# PCBPhase.net
KiCad netlist of a schematic drawn in EasyEDA Pro
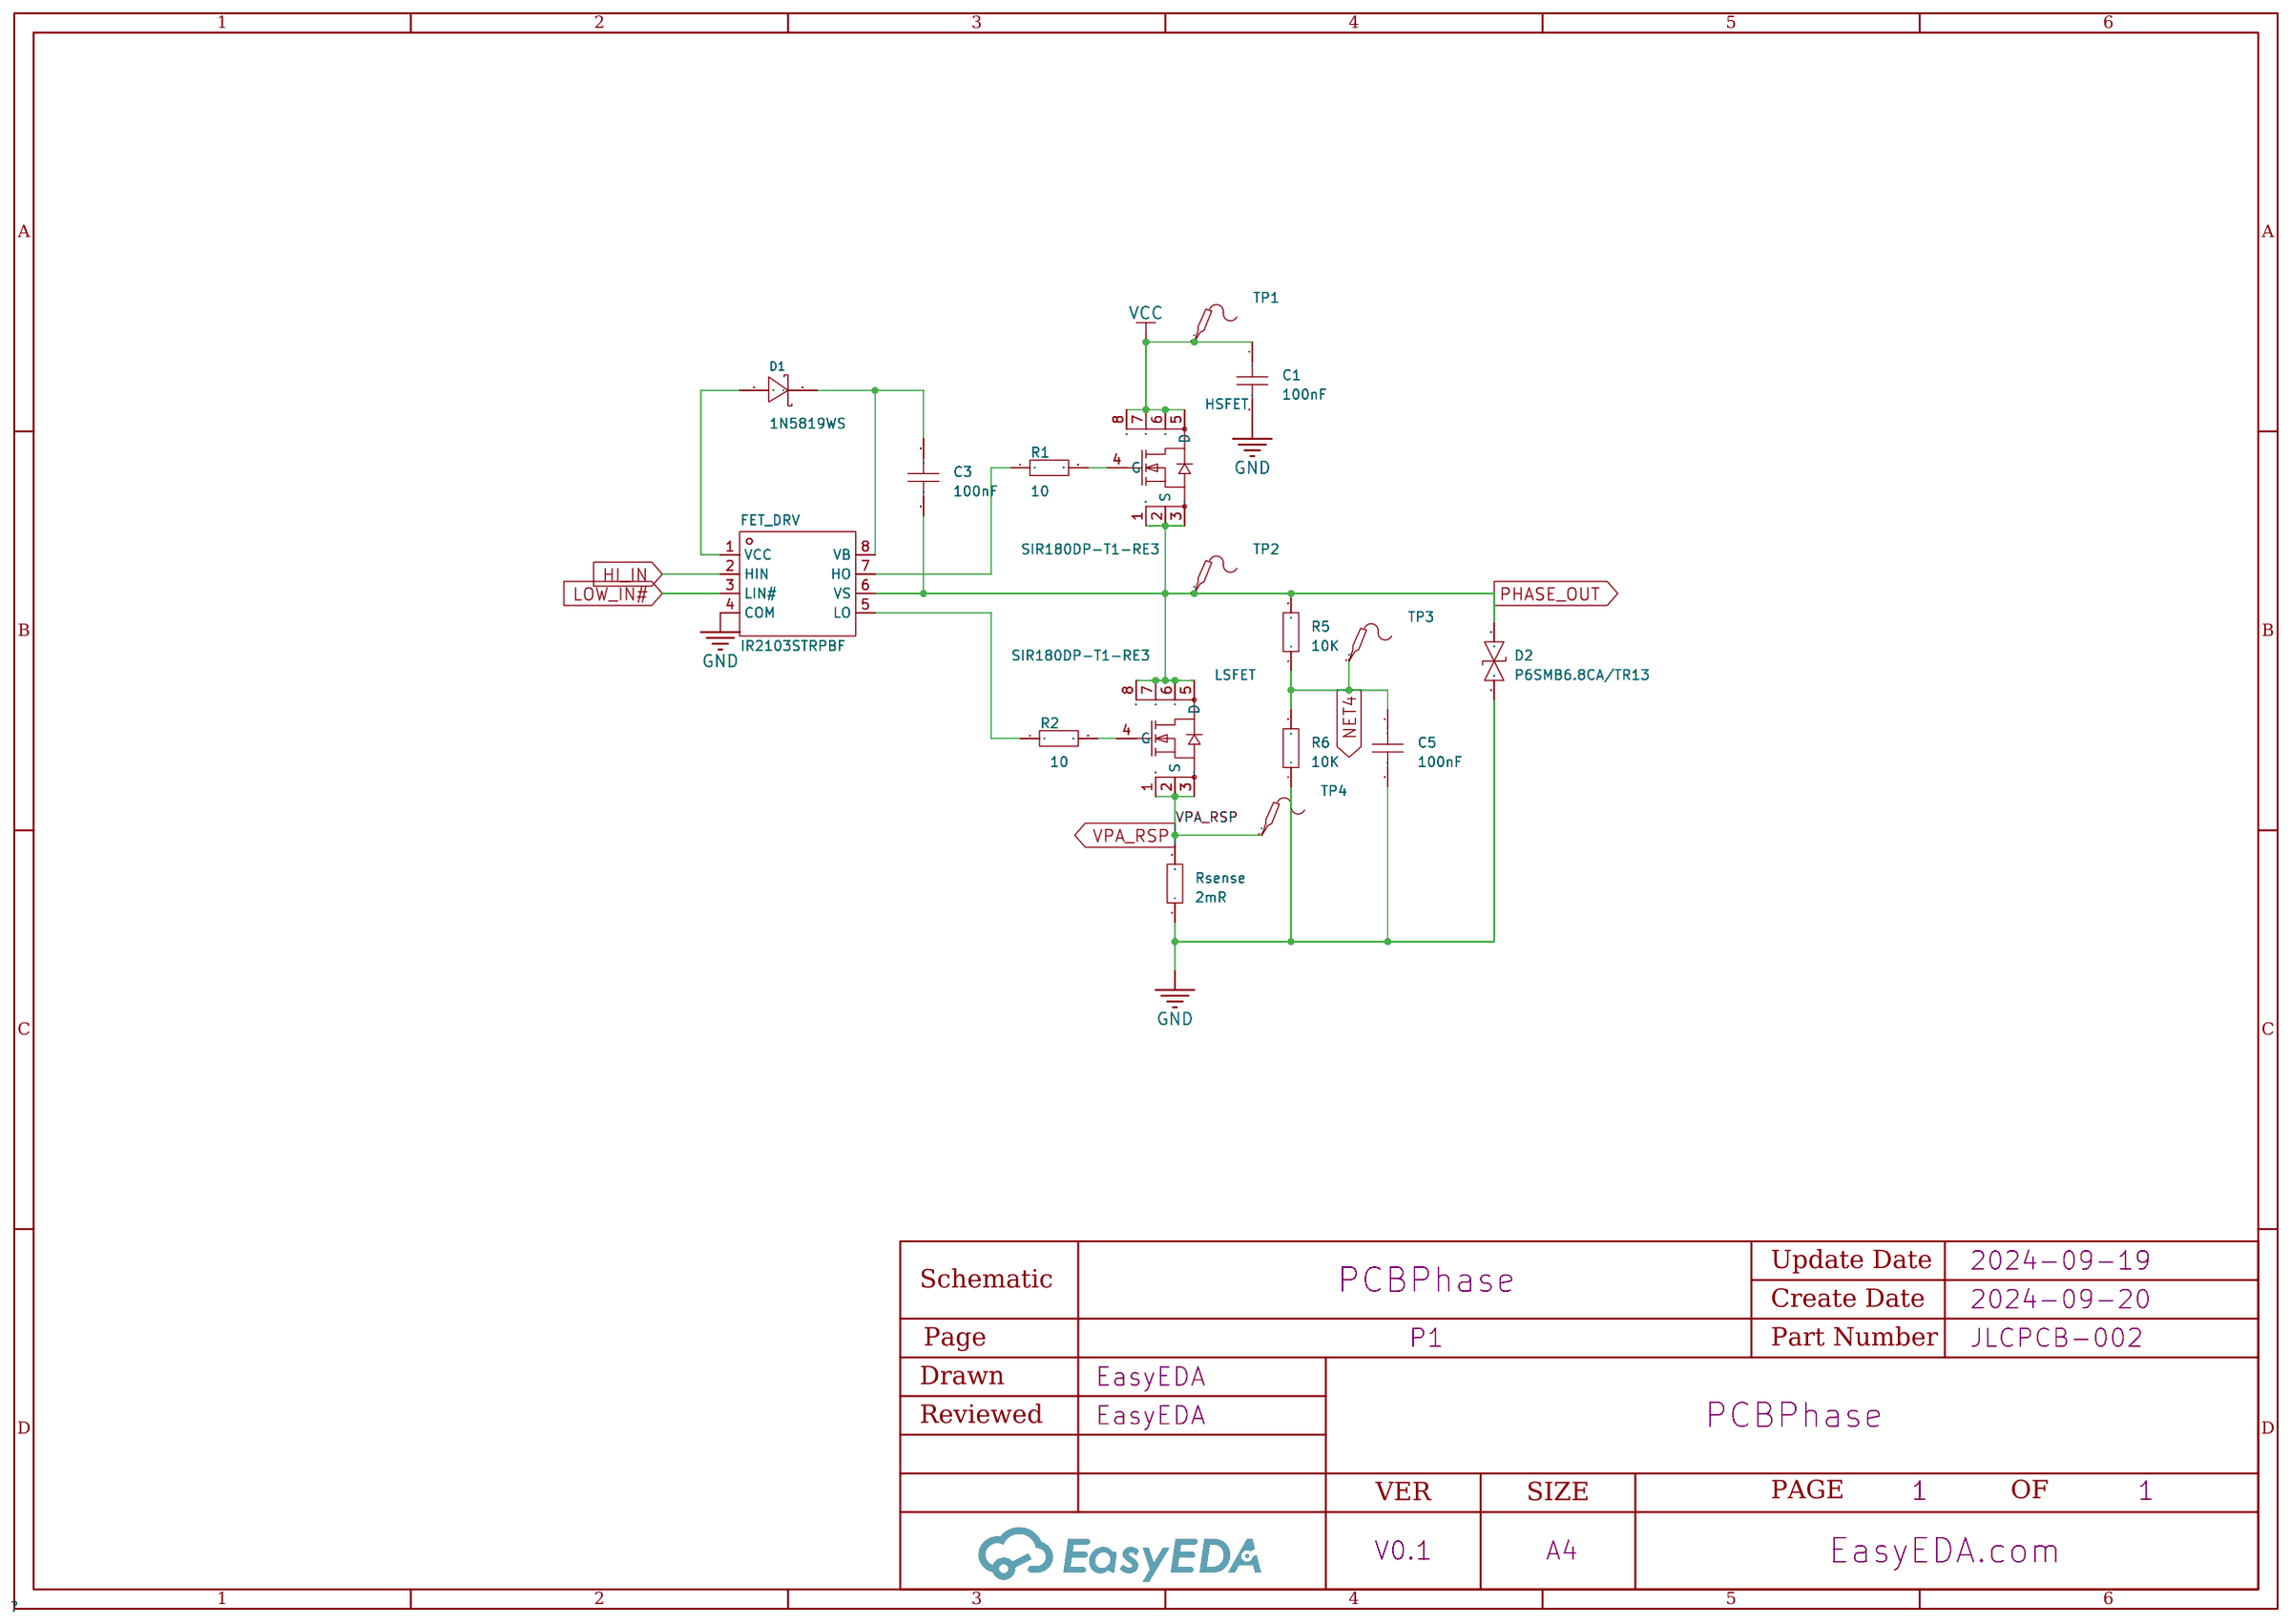
[diagram p0: schematic sheet]

(export (version "E")
  (design (tool "Eeschema 10.0.6"))
  (components
    (comp (ref "C1")
      (value "100nF")
      (footprint "easyedapro:C0603")
      (libsource (lib "easyedapro") (part "CAP"))
    )
    (comp (ref "C3")
      (value "100nF")
      (footprint "easyedapro:C0603")
      (libsource (lib "easyedapro") (part "CAP"))
    )
    (comp (ref "C5")
      (value "100nF")
      (footprint "easyedapro:C0603")
      (libsource (lib "easyedapro") (part "CAP"))
    )
    (comp (ref "D1")
      (value "1N5819WS")
      (footprint "easyedapro:SOD-323_L1.8-W1.3-LS2.5-RD")
      (description "Forward Voltage (Vf@If):600mV@1A Reverse Voltage (Vr):40V Average Rectified Current (Io):1A")
      (fields (field (name "Manufacturer") "Hottech(合科泰)"))
      (libsource (lib "easyedapro") (part "1N5819WS"))
    )
    (comp (ref "D2")
      (value "P6SMB6.8CA/TR13")
      (footprint "easyedapro:SMB_L4.6-W3.6-LS5.3-BI")
      (fields (field (name "Manufacturer") "Brightking(君耀电子)"))
      (libsource (lib "easyedapro") (part "P6SMB6.8CA-C78395"))
    )
    (comp (ref "FET_DRV")
      (value "IR2103STRPBF")
      (footprint "easyedapro:SOIC-8_L4.9-W3.9-P1.27-LS6.0-BL")
      (fields (field (name "Manufacturer") "Infineon(英飞凌)"))
      (libsource (lib "easyedapro") (part "IR2103STRPBF"))
    )
    (comp (ref "HSFET")
      (value "SIR180DP-T1-RE3")
      (footprint "easyedapro:POWERPAK-SO-8_L5.9-W4.9-P1.27-LS6.2-BL")
      (fields (field (name "Manufacturer") "VISHAY(威世)"))
      (libsource (lib "easyedapro") (part "SIR180DP-T1-RE3"))
    )
    (comp (ref "LSFET")
      (value "SIR180DP-T1-RE3")
      (footprint "easyedapro:POWERPAK-SO-8_L5.9-W4.9-P1.27-LS6.2-BL")
      (fields (field (name "Manufacturer") "VISHAY(威世)"))
      (libsource (lib "easyedapro") (part "SIR180DP-T1-RE3"))
    )
    (comp (ref "R1") (value "10") (footprint "easyedapro:R0603") (libsource (lib "easyedapro") (part "Res")))
    (comp (ref "R2") (value "10") (footprint "easyedapro:R0603") (libsource (lib "easyedapro") (part "Res")))
    (comp (ref "R5") (value "10K") (footprint "easyedapro:R0603") (libsource (lib "easyedapro") (part "Res")))
    (comp (ref "R6") (value "10K") (footprint "easyedapro:R0603") (libsource (lib "easyedapro") (part "Res")))
    (comp (ref "Rsense")
      (value "2mR")
      (footprint "easyedapro:R0603")
      (libsource (lib "easyedapro") (part "Res"))
    )
    (comp (ref "TP1")
      (value "~")
      (footprint "easyedapro:Test-Point-0.5mm")
      (description "Test Point 测试点")
      (libsource (lib "easyedapro") (part "Test-Point"))
    )
    (comp (ref "TP2")
      (value "~")
      (footprint "easyedapro:Test-Point-0.5mm")
      (description "Test Point 测试点")
      (libsource (lib "easyedapro") (part "Test-Point"))
    )
    (comp (ref "TP3")
      (value "~")
      (footprint "easyedapro:Test-Point-0.5mm")
      (description "Test Point 测试点")
      (libsource (lib "easyedapro") (part "Test-Point"))
    )
    (comp (ref "TP4")
      (value "~")
      (footprint "easyedapro:Test-Point-0.5mm")
      (description "Test Point 测试点")
      (libsource (lib "easyedapro") (part "Test-Point"))
    )
  )
  (nets
    (net (code "1") (name "GND") (class "Default")
      (node (ref "C1") (pin "2") (pinfunction "2_2") (pintype "input"))
      (node (ref "C5") (pin "2") (pinfunction "2_2") (pintype "input"))
      (node (ref "D2") (pin "1") (pinfunction "1_1") (pintype "unspecified"))
      (node (ref "FET_DRV") (pin "4") (pinfunction "COM_4") (pintype "unspecified"))
      (node (ref "R6") (pin "1") (pinfunction "1_1") (pintype "input"))
      (node (ref "Rsense") (pin "1") (pinfunction "1_1") (pintype "input"))
    )
    (net (code "2") (name "HI_IN") (class "Default")
      (node (ref "FET_DRV") (pin "2") (pinfunction "HIN_2") (pintype "unspecified"))
    )
    (net (code "3") (name "LOW_IN#") (class "Default")
      (node (ref "FET_DRV") (pin "3") (pinfunction "LIN#_3") (pintype "unspecified"))
    )
    (net (code "4") (name "NET4") (class "Default")
      (node (ref "C5") (pin "1") (pinfunction "1_1") (pintype "input"))
      (node (ref "R5") (pin "1") (pinfunction "1_1") (pintype "input"))
      (node (ref "R6") (pin "2") (pinfunction "2_2") (pintype "input"))
      (node (ref "TP3") (pin "1") (pinfunction "1_1") (pintype "unspecified"))
    )
    (net (code "5") (name "Net-(D1-A)") (class "Default")
      (node (ref "D1") (pin "2") (pinfunction "A_2") (pintype "input"))
      (node (ref "FET_DRV") (pin "1") (pinfunction "VCC_1") (pintype "unspecified"))
    )
    (net (code "6") (name "Net-(D1-K)") (class "Default")
      (node (ref "C3") (pin "1") (pinfunction "1_1") (pintype "input"))
      (node (ref "D1") (pin "1") (pinfunction "K_1") (pintype "input"))
      (node (ref "FET_DRV") (pin "8") (pinfunction "VB_8") (pintype "unspecified"))
    )
    (net (code "7") (name "Net-(FET_DRV-HO)") (class "Default")
      (node (ref "FET_DRV") (pin "7") (pinfunction "HO_7") (pintype "unspecified"))
      (node (ref "R1") (pin "1") (pinfunction "1_1") (pintype "input"))
    )
    (net (code "8") (name "Net-(FET_DRV-LO)") (class "Default")
      (node (ref "FET_DRV") (pin "5") (pinfunction "LO_5") (pintype "unspecified"))
      (node (ref "R2") (pin "1") (pinfunction "1_1") (pintype "input"))
    )
    (net (code "9") (name "Net-(HSFET-G)") (class "Default")
      (node (ref "HSFET") (pin "4") (pinfunction "G_4") (pintype "unspecified"))
      (node (ref "R1") (pin "2") (pinfunction "2_2") (pintype "input"))
    )
    (net (code "10") (name "Net-(LSFET-G)") (class "Default")
      (node (ref "LSFET") (pin "4") (pinfunction "G_4") (pintype "unspecified"))
      (node (ref "R2") (pin "2") (pinfunction "2_2") (pintype "input"))
    )
    (net (code "11") (name "PHASE_OUT") (class "Default")
      (node (ref "C3") (pin "2") (pinfunction "2_2") (pintype "input"))
      (node (ref "D2") (pin "2") (pinfunction "2_2") (pintype "unspecified"))
      (node (ref "FET_DRV") (pin "6") (pinfunction "VS_6") (pintype "unspecified"))
      (node (ref "HSFET") (pin "1") (pinfunction "S_1") (pintype "unspecified"))
      (node (ref "HSFET") (pin "2") (pinfunction "S_2") (pintype "unspecified"))
      (node (ref "HSFET") (pin "3") (pinfunction "S_3") (pintype "unspecified"))
      (node (ref "LSFET") (pin "5") (pinfunction "D_5") (pintype "unspecified"))
      (node (ref "LSFET") (pin "6") (pinfunction "D_6") (pintype "unspecified"))
      (node (ref "LSFET") (pin "7") (pinfunction "D_7") (pintype "unspecified"))
      (node (ref "LSFET") (pin "8") (pinfunction "D_8") (pintype "unspecified"))
      (node (ref "R5") (pin "2") (pinfunction "2_2") (pintype "input"))
      (node (ref "TP2") (pin "1") (pinfunction "1_1") (pintype "unspecified"))
    )
    (net (code "12") (name "VCC") (class "Default")
      (node (ref "C1") (pin "1") (pinfunction "1_1") (pintype "input"))
      (node (ref "HSFET") (pin "5") (pinfunction "D_5") (pintype "unspecified"))
      (node (ref "HSFET") (pin "6") (pinfunction "D_6") (pintype "unspecified"))
      (node (ref "HSFET") (pin "7") (pinfunction "D_7") (pintype "unspecified"))
      (node (ref "HSFET") (pin "8") (pinfunction "D_8") (pintype "unspecified"))
      (node (ref "TP1") (pin "1") (pinfunction "1_1") (pintype "unspecified"))
    )
    (net (code "13") (name "VPA_RSP") (class "Default")
      (node (ref "LSFET") (pin "1") (pinfunction "S_1") (pintype "unspecified"))
      (node (ref "LSFET") (pin "2") (pinfunction "S_2") (pintype "unspecified"))
      (node (ref "LSFET") (pin "3") (pinfunction "S_3") (pintype "unspecified"))
      (node (ref "Rsense") (pin "2") (pinfunction "2_2") (pintype "input"))
      (node (ref "TP4") (pin "1") (pinfunction "1_1") (pintype "unspecified"))
    )
  )
)
